# tail.net
KiCad netlist of a schematic drawn in EAGLE
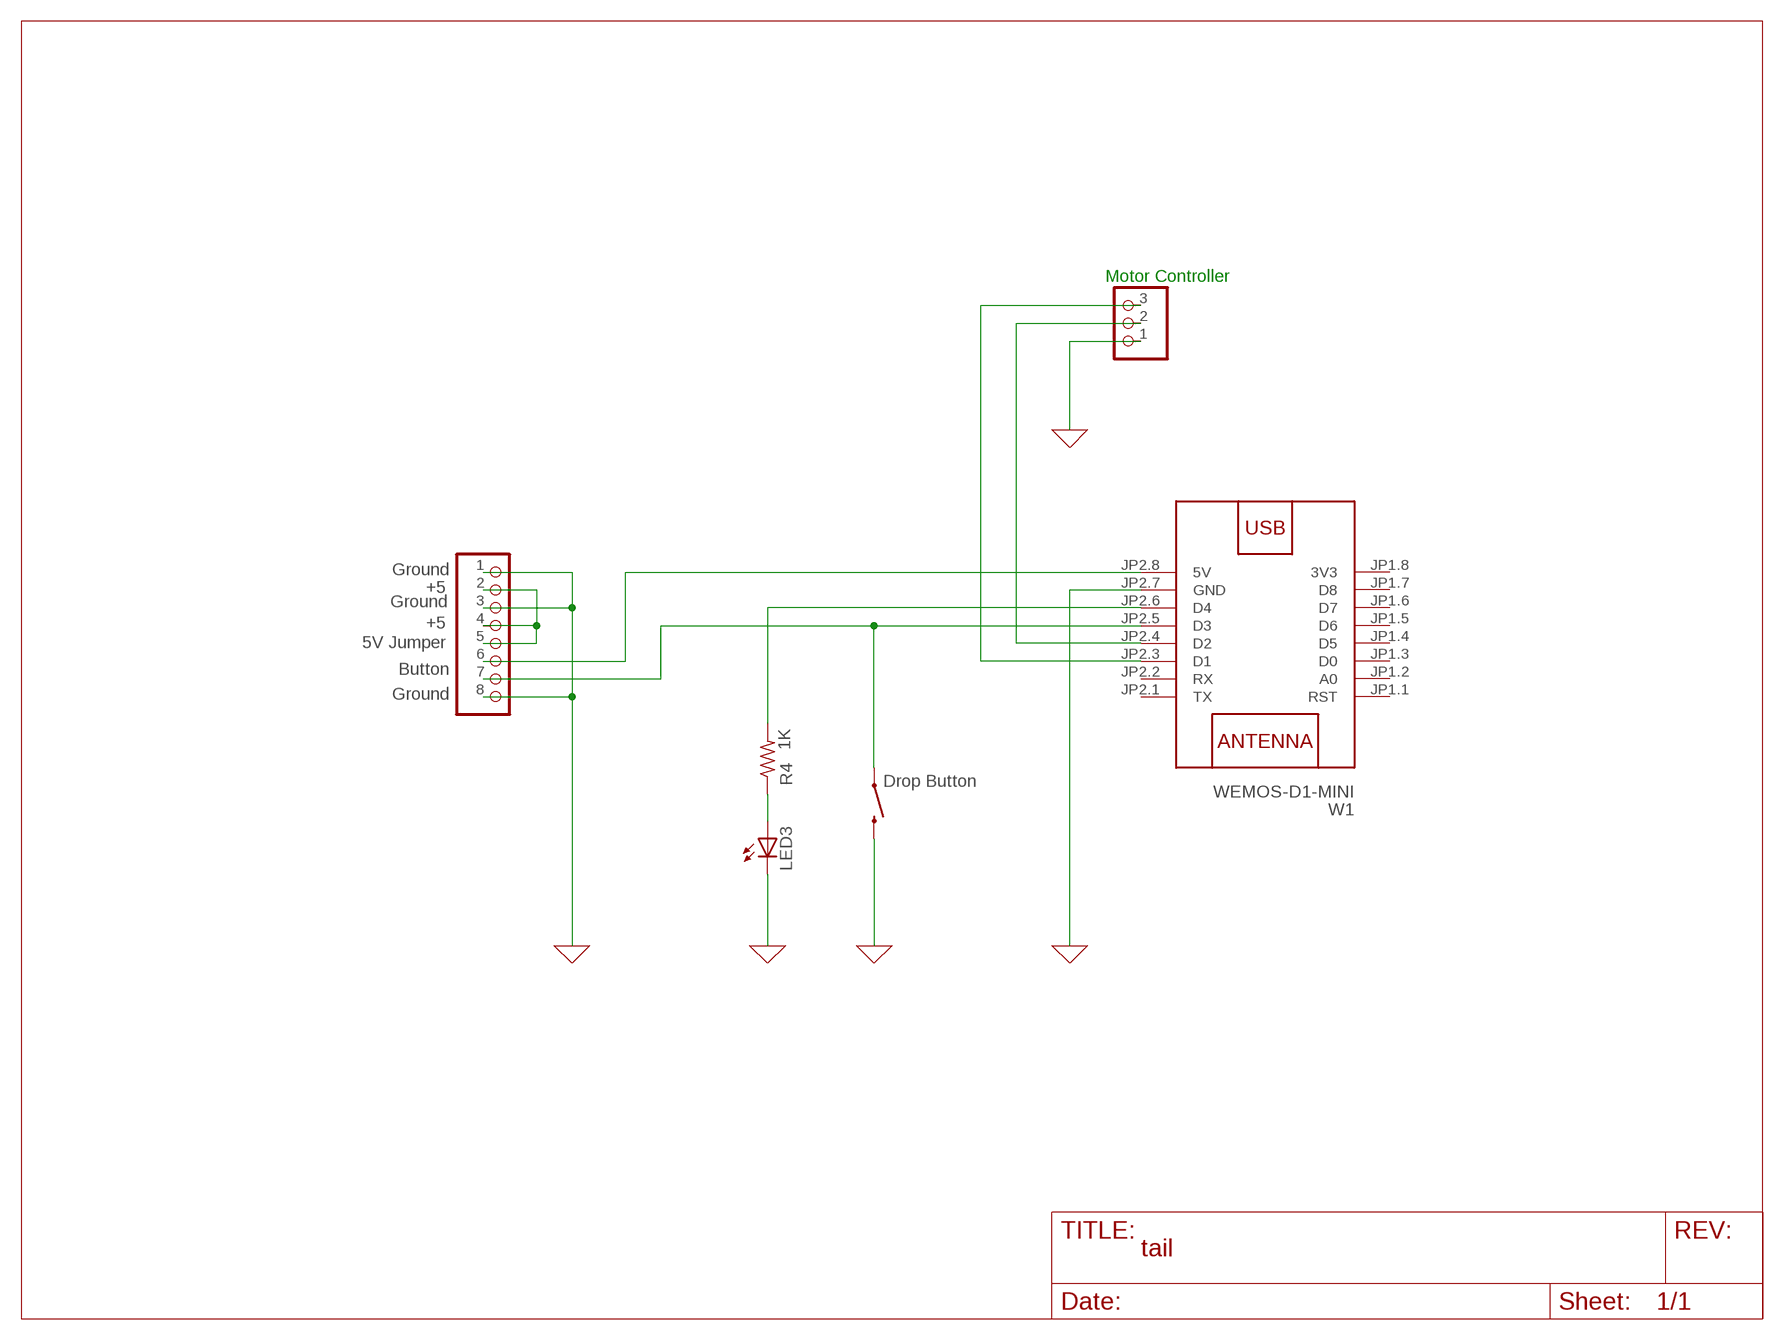
[diagram p0: schematic, sheet 1]

(export (version "E")
  (design (tool "Eeschema 10.0.6"))
  (components
    (comp (ref "JP1")
      (value "PINHD-1X8BIG")
      (footprint "eagle-import:1X08-BIG")
      (libsource (lib "eagle-import") (part "PINHD-1X8BIG"))
    )
    (comp (ref "JP2")
      (value "PINHD-1X3")
      (footprint "eagle-import:1X03")
      (libsource (lib "eagle-import") (part "PINHD-1X3"))
    )
    (comp (ref "LED3")
      (value "LED5MM")
      (footprint "eagle-import:LED5MM")
      (libsource (lib "eagle-import") (part "LED5MM"))
    )
    (comp (ref "R4")
      (value "1K")
      (footprint "eagle-import:0207_10")
      (libsource (lib "eagle-import") (part "R-US_0207/10"))
    )
    (comp (ref "S1")
      (value "MOMENTARY-SWITCH-SPST-PTH-6.0MM")
      (footprint "eagle-import:TACTILE_SWITCH_PTH_6.0MM")
      (libsource (lib "eagle-import") (part "MOMENTARY-SWITCH-SPST-PTH-6.0MM"))
    )
    (comp (ref "W1")
      (value "WEMOS-D1-MINI")
      (footprint "eagle-import:WEMOS-D1-MINI")
      (libsource (lib "eagle-import") (part "WEMOS-D1-MINI"))
    )
  )
  (nets
    (net (code "1") (name "/3V3") (class "Default")
      (node (ref "W1") (pin "JP1.8") (pinfunction "3V3_JP1.8") (pintype "power_in"))
    )
    (net (code "2") (name "GND") (class "Default")
      (node (ref "JP1") (pin "1") (pinfunction "1_1") (pintype "passive"))
      (node (ref "JP1") (pin "3") (pinfunction "3_3") (pintype "passive"))
      (node (ref "JP1") (pin "8") (pinfunction "8_8") (pintype "passive"))
      (node (ref "JP2") (pin "1") (pinfunction "1_1") (pintype "passive"))
      (node (ref "LED3") (pin "K") (pinfunction "C_K") (pintype "passive"))
      (node (ref "S1") (pin "3") (pinfunction "2_3") (pintype "passive"))
      (node (ref "W1") (pin "JP2.7") (pinfunction "GND_JP2.7") (pintype "power_in"))
    )
    (net (code "3") (name "Net-(JP1-Pad2)") (class "Default")
      (node (ref "JP1") (pin "2") (pinfunction "2_2") (pintype "passive"))
      (node (ref "JP1") (pin "4") (pinfunction "4_4") (pintype "passive"))
      (node (ref "JP1") (pin "5") (pinfunction "5_5") (pintype "passive"))
    )
    (net (code "4") (name "Net-(LED3-PadA)") (class "Default")
      (node (ref "LED3") (pin "A") (pinfunction "A_A") (pintype "passive"))
      (node (ref "R4") (pin "1") (pinfunction "1_1") (pintype "passive"))
    )
    (net (code "5") (name "Net-(W1-5V)") (class "Default")
      (node (ref "JP1") (pin "6") (pinfunction "6_6") (pintype "passive"))
      (node (ref "W1") (pin "JP2.8") (pinfunction "5V_JP2.8") (pintype "power_in"))
    )
    (net (code "6") (name "Net-(W1-D1)") (class "Default")
      (node (ref "JP2") (pin "3") (pinfunction "3_3") (pintype "passive"))
      (node (ref "W1") (pin "JP2.3") (pinfunction "D1_JP2.3") (pintype "bidirectional"))
    )
    (net (code "7") (name "Net-(W1-D2)") (class "Default")
      (node (ref "JP2") (pin "2") (pinfunction "2_2") (pintype "passive"))
      (node (ref "W1") (pin "JP2.4") (pinfunction "D2_JP2.4") (pintype "bidirectional"))
    )
    (net (code "8") (name "Net-(W1-D3)") (class "Default")
      (node (ref "JP1") (pin "7") (pinfunction "7_7") (pintype "passive"))
      (node (ref "S1") (pin "1") (pinfunction "1_1") (pintype "passive"))
      (node (ref "W1") (pin "JP2.5") (pinfunction "D3_JP2.5") (pintype "bidirectional"))
    )
    (net (code "9") (name "Net-(W1-D4)") (class "Default")
      (node (ref "R4") (pin "2") (pinfunction "2_2") (pintype "passive"))
      (node (ref "W1") (pin "JP2.6") (pinfunction "D4_JP2.6") (pintype "bidirectional"))
    )
    (net (code "10") (name "unconnected-(W1-A0-PadJP1.2)") (class "Default")
      (node (ref "W1") (pin "JP1.2") (pinfunction "A0_JP1.2") (pintype "bidirectional"))
    )
    (net (code "11") (name "unconnected-(W1-D0-PadJP1.3)") (class "Default")
      (node (ref "W1") (pin "JP1.3") (pinfunction "D0_JP1.3") (pintype "bidirectional"))
    )
    (net (code "12") (name "unconnected-(W1-D5-PadJP1.4)") (class "Default")
      (node (ref "W1") (pin "JP1.4") (pinfunction "D5_JP1.4") (pintype "bidirectional"))
    )
    (net (code "13") (name "unconnected-(W1-D6-PadJP1.5)") (class "Default")
      (node (ref "W1") (pin "JP1.5") (pinfunction "D6_JP1.5") (pintype "bidirectional"))
    )
    (net (code "14") (name "unconnected-(W1-D7-PadJP1.6)") (class "Default")
      (node (ref "W1") (pin "JP1.6") (pinfunction "D7_JP1.6") (pintype "bidirectional"))
    )
    (net (code "15") (name "unconnected-(W1-D8-PadJP1.7)") (class "Default")
      (node (ref "W1") (pin "JP1.7") (pinfunction "D8_JP1.7") (pintype "bidirectional"))
    )
    (net (code "16") (name "unconnected-(W1-RST-PadJP1.1)") (class "Default")
      (node (ref "W1") (pin "JP1.1") (pinfunction "RST_JP1.1") (pintype "bidirectional"))
    )
    (net (code "17") (name "unconnected-(W1-RX-PadJP2.2)") (class "Default")
      (node (ref "W1") (pin "JP2.2") (pinfunction "RX_JP2.2") (pintype "bidirectional"))
    )
    (net (code "18") (name "unconnected-(W1-TX-PadJP2.1)") (class "Default")
      (node (ref "W1") (pin "JP2.1") (pinfunction "TX_JP2.1") (pintype "bidirectional"))
    )
  )
)
